# Logoi.net
KiCad netlist of a schematic drawn in EAGLE
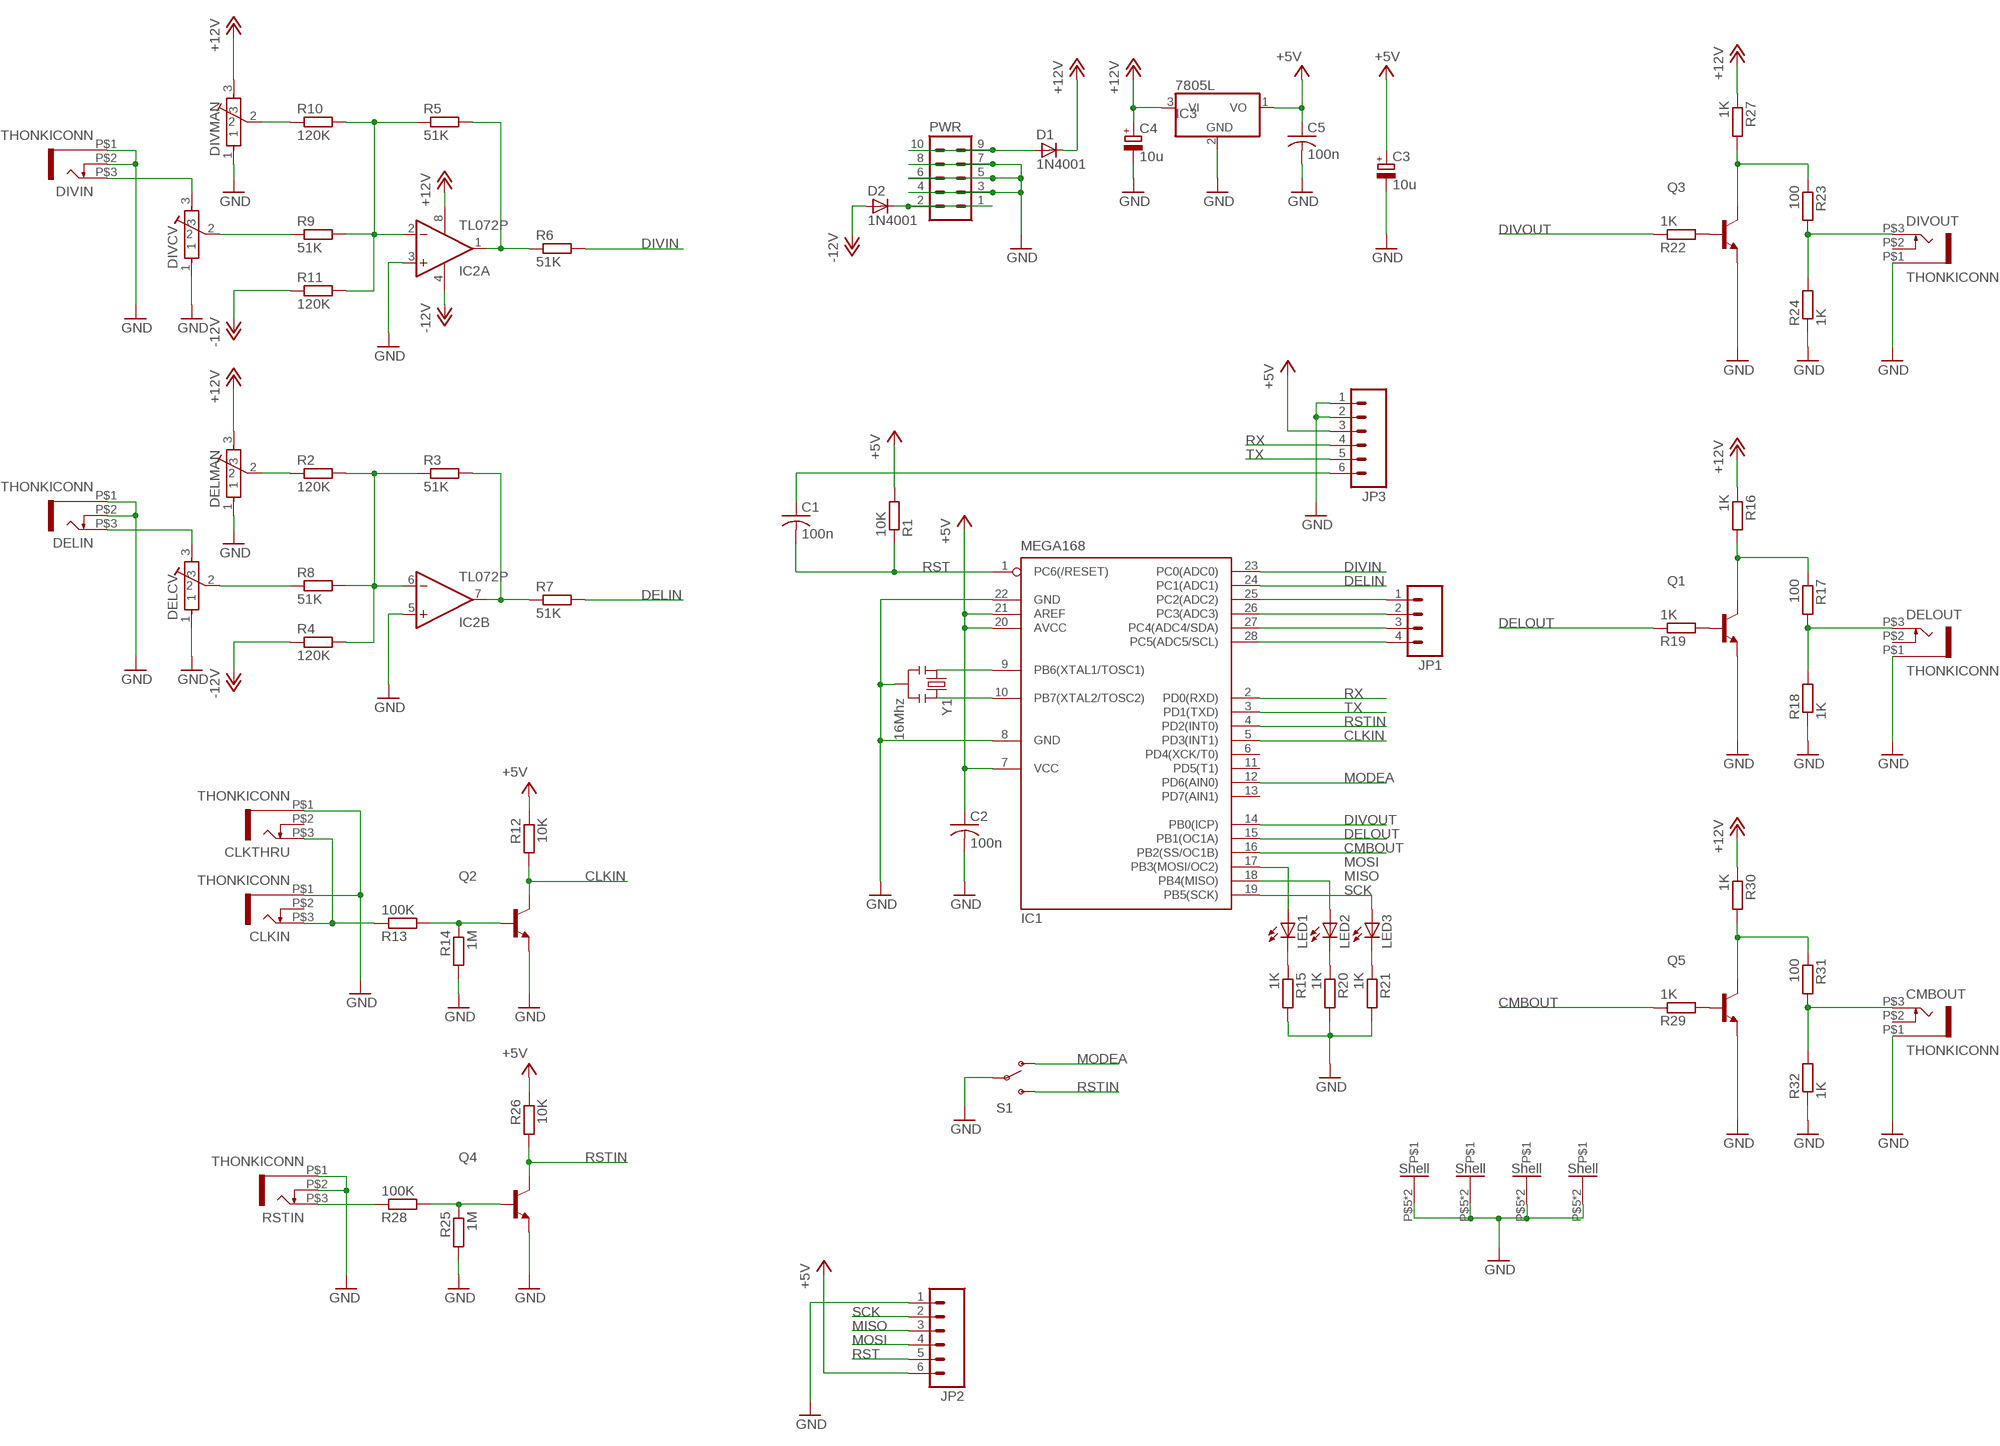
[diagram p0: schematic, sheet 1]

(export (version "E")
  (design (tool "Eeschema 10.0.6"))
  (components
    (comp (ref "C1")
      (value "100n")
      (footprint "eagle-import:C050-024X044")
      (libsource (lib "eagle-import") (part "C-US050-024X044"))
    )
    (comp (ref "C2")
      (value "100n")
      (footprint "eagle-import:C050-024X044")
      (libsource (lib "eagle-import") (part "C-US050-024X044"))
    )
    (comp (ref "C3")
      (value "10u")
      (footprint "eagle-import:E5-6")
      (libsource (lib "eagle-import") (part "CPOL-EUE5-6"))
    )
    (comp (ref "C4")
      (value "10u")
      (footprint "eagle-import:E5-6")
      (libsource (lib "eagle-import") (part "CPOL-EUE5-6"))
    )
    (comp (ref "C5")
      (value "100n")
      (footprint "eagle-import:C050-024X044")
      (libsource (lib "eagle-import") (part "C-US050-024X044"))
    )
    (comp (ref "CLKIN")
      (value "THONKICONN")
      (footprint "eagle-import:THONKICONN")
      (libsource (lib "eagle-import") (part "THONKICONN"))
    )
    (comp (ref "CLKTHRU")
      (value "THONKICONN")
      (footprint "eagle-import:THONKICONN")
      (libsource (lib "eagle-import") (part "THONKICONN"))
    )
    (comp (ref "CMBOUT")
      (value "THONKICONN")
      (footprint "eagle-import:THONKICONN")
      (libsource (lib "eagle-import") (part "THONKICONN"))
    )
    (comp (ref "D1")
      (value "1N4001")
      (footprint "eagle-import:DIODE-1N4001")
      (libsource (lib "eagle-import") (part "DIODE1N4001"))
    )
    (comp (ref "D2")
      (value "1N4001")
      (footprint "eagle-import:DIODE-1N4001")
      (libsource (lib "eagle-import") (part "DIODE1N4001"))
    )
    (comp (ref "DELCV")
      (value "POT-ALPS-RK09L1140")
      (footprint "eagle-import:POT-ALPS-RK09L1140")
      (libsource (lib "eagle-import") (part "POT-ALPS-RK09L1140"))
    )
    (comp (ref "DELIN")
      (value "THONKICONN")
      (footprint "eagle-import:THONKICONN")
      (libsource (lib "eagle-import") (part "THONKICONN"))
    )
    (comp (ref "DELMAN")
      (value "POT-ALPS-RK09L1140")
      (footprint "eagle-import:POT-ALPS-RK09L1140")
      (libsource (lib "eagle-import") (part "POT-ALPS-RK09L1140"))
    )
    (comp (ref "DELOUT")
      (value "THONKICONN")
      (footprint "eagle-import:THONKICONN")
      (libsource (lib "eagle-import") (part "THONKICONN"))
    )
    (comp (ref "DIVCV")
      (value "POT-ALPS-RK09L1140")
      (footprint "eagle-import:POT-ALPS-RK09L1140")
      (libsource (lib "eagle-import") (part "POT-ALPS-RK09L1140"))
    )
    (comp (ref "DIVIN")
      (value "THONKICONN")
      (footprint "eagle-import:THONKICONN")
      (libsource (lib "eagle-import") (part "THONKICONN"))
    )
    (comp (ref "DIVMAN")
      (value "POT-ALPS-RK09L1140")
      (footprint "eagle-import:POT-ALPS-RK09L1140")
      (libsource (lib "eagle-import") (part "POT-ALPS-RK09L1140"))
    )
    (comp (ref "DIVOUT")
      (value "THONKICONN")
      (footprint "eagle-import:THONKICONN")
      (libsource (lib "eagle-import") (part "THONKICONN"))
    )
    (comp (ref "IC1")
      (value "MEGA168")
      (footprint "eagle-import:DIL28-3")
      (libsource (lib "eagle-import") (part "MEGA8-P"))
    )
    (comp (ref "IC2")
      (value "TL072P")
      (footprint "eagle-import:DIL08")
      (libsource (lib "eagle-import") (part "TL072P"))
    )
    (comp (ref "IC3")
      (value "7805L")
      (footprint "eagle-import:TO92")
      (libsource (lib "eagle-import") (part "78L05"))
    )
    (comp (ref "JP1")
      (value "M04PTH")
      (footprint "eagle-import:1X04")
      (libsource (lib "eagle-import") (part "M04PTH"))
    )
    (comp (ref "JP2")
      (value "M06SIP")
      (footprint "eagle-import:1X06")
      (libsource (lib "eagle-import") (part "M06SIP"))
    )
    (comp (ref "JP3")
      (value "M06SIP")
      (footprint "eagle-import:1X06")
      (libsource (lib "eagle-import") (part "M06SIP"))
    )
    (comp (ref "LED1")
      (value "LED3MM")
      (footprint "eagle-import:LED3MM")
      (libsource (lib "eagle-import") (part "LED3MM"))
    )
    (comp (ref "LED2")
      (value "LED3MM")
      (footprint "eagle-import:LED3MM")
      (libsource (lib "eagle-import") (part "LED3MM"))
    )
    (comp (ref "LED3")
      (value "LED3MM")
      (footprint "eagle-import:LED3MM")
      (libsource (lib "eagle-import") (part "LED3MM"))
    )
    (comp (ref "PWR")
      (value "MA05-2")
      (footprint "eagle-import:MA05-2")
      (libsource (lib "eagle-import") (part "MA05-2"))
    )
    (comp (ref "Q1")
      (value "2N3904-NPN-TO92-EBC")
      (footprint "eagle-import:TO92-EBC")
      (libsource (lib "eagle-import") (part "-NPN-TO92-EBC2N3904"))
    )
    (comp (ref "Q2")
      (value "2N3904-NPN-TO92-EBC")
      (footprint "eagle-import:TO92-EBC")
      (libsource (lib "eagle-import") (part "-NPN-TO92-EBC2N3904"))
    )
    (comp (ref "Q3")
      (value "2N3904-NPN-TO92-EBC")
      (footprint "eagle-import:TO92-EBC")
      (libsource (lib "eagle-import") (part "-NPN-TO92-EBC2N3904"))
    )
    (comp (ref "Q4")
      (value "2N3904-NPN-TO92-EBC")
      (footprint "eagle-import:TO92-EBC")
      (libsource (lib "eagle-import") (part "-NPN-TO92-EBC2N3904"))
    )
    (comp (ref "Q5")
      (value "2N3904-NPN-TO92-EBC")
      (footprint "eagle-import:TO92-EBC")
      (libsource (lib "eagle-import") (part "-NPN-TO92-EBC2N3904"))
    )
    (comp (ref "R1")
      (value "10K")
      (footprint "eagle-import:0204_7")
      (libsource (lib "eagle-import") (part "R-EU_0204/7"))
    )
    (comp (ref "R2")
      (value "120K")
      (footprint "eagle-import:0204_7")
      (libsource (lib "eagle-import") (part "R-EU_0204/7"))
    )
    (comp (ref "R3")
      (value "51K")
      (footprint "eagle-import:0204_7")
      (libsource (lib "eagle-import") (part "R-EU_0204/7"))
    )
    (comp (ref "R4")
      (value "120K")
      (footprint "eagle-import:0204_7")
      (libsource (lib "eagle-import") (part "R-EU_0204/7"))
    )
    (comp (ref "R5")
      (value "51K")
      (footprint "eagle-import:0204_7")
      (libsource (lib "eagle-import") (part "R-EU_0204/7"))
    )
    (comp (ref "R6")
      (value "51K")
      (footprint "eagle-import:0204_7")
      (libsource (lib "eagle-import") (part "R-EU_0204/7"))
    )
    (comp (ref "R7")
      (value "51K")
      (footprint "eagle-import:0204_7")
      (libsource (lib "eagle-import") (part "R-EU_0204/7"))
    )
    (comp (ref "R8")
      (value "51K")
      (footprint "eagle-import:0204_7")
      (libsource (lib "eagle-import") (part "R-EU_0204/7"))
    )
    (comp (ref "R9")
      (value "51K")
      (footprint "eagle-import:0204_7")
      (libsource (lib "eagle-import") (part "R-EU_0204/7"))
    )
    (comp (ref "R10")
      (value "120K")
      (footprint "eagle-import:0204_7")
      (libsource (lib "eagle-import") (part "R-EU_0204/7"))
    )
    (comp (ref "R11")
      (value "120K")
      (footprint "eagle-import:0204_7")
      (libsource (lib "eagle-import") (part "R-EU_0204/7"))
    )
    (comp (ref "R12")
      (value "10K")
      (footprint "eagle-import:0204_7")
      (libsource (lib "eagle-import") (part "R-EU_0204/7"))
    )
    (comp (ref "R13")
      (value "100K")
      (footprint "eagle-import:0204_7")
      (libsource (lib "eagle-import") (part "R-EU_0204/7"))
    )
    (comp (ref "R14")
      (value "1M")
      (footprint "eagle-import:0204_7")
      (libsource (lib "eagle-import") (part "R-EU_0204/7"))
    )
    (comp (ref "R15")
      (value "1K")
      (footprint "eagle-import:0204_7")
      (libsource (lib "eagle-import") (part "R-EU_0204/7"))
    )
    (comp (ref "R16")
      (value "1K")
      (footprint "eagle-import:0204_7")
      (libsource (lib "eagle-import") (part "R-EU_0204/7"))
    )
    (comp (ref "R17")
      (value "100")
      (footprint "eagle-import:0204_7")
      (libsource (lib "eagle-import") (part "R-EU_0204/7"))
    )
    (comp (ref "R18")
      (value "1K")
      (footprint "eagle-import:0204_7")
      (libsource (lib "eagle-import") (part "R-EU_0204/7"))
    )
    (comp (ref "R19")
      (value "1K")
      (footprint "eagle-import:0204_7")
      (libsource (lib "eagle-import") (part "R-EU_0204/7"))
    )
    (comp (ref "R20")
      (value "1K")
      (footprint "eagle-import:0204_7")
      (libsource (lib "eagle-import") (part "R-EU_0204/7"))
    )
    (comp (ref "R21")
      (value "1K")
      (footprint "eagle-import:0204_7")
      (libsource (lib "eagle-import") (part "R-EU_0204/7"))
    )
    (comp (ref "R22")
      (value "1K")
      (footprint "eagle-import:0204_7")
      (libsource (lib "eagle-import") (part "R-EU_0204/7"))
    )
    (comp (ref "R23")
      (value "100")
      (footprint "eagle-import:0204_7")
      (libsource (lib "eagle-import") (part "R-EU_0204/7"))
    )
    (comp (ref "R24")
      (value "1K")
      (footprint "eagle-import:0204_7")
      (libsource (lib "eagle-import") (part "R-EU_0204/7"))
    )
    (comp (ref "R25")
      (value "1M")
      (footprint "eagle-import:0204_7")
      (libsource (lib "eagle-import") (part "R-EU_0204/7"))
    )
    (comp (ref "R26")
      (value "10K")
      (footprint "eagle-import:0204_7")
      (libsource (lib "eagle-import") (part "R-EU_0204/7"))
    )
    (comp (ref "R27")
      (value "1K")
      (footprint "eagle-import:0204_7")
      (libsource (lib "eagle-import") (part "R-EU_0204/7"))
    )
    (comp (ref "R28")
      (value "100K")
      (footprint "eagle-import:0204_7")
      (libsource (lib "eagle-import") (part "R-EU_0204/7"))
    )
    (comp (ref "R29")
      (value "1K")
      (footprint "eagle-import:0204_7")
      (libsource (lib "eagle-import") (part "R-EU_0204/7"))
    )
    (comp (ref "R30")
      (value "1K")
      (footprint "eagle-import:0204_7")
      (libsource (lib "eagle-import") (part "R-EU_0204/7"))
    )
    (comp (ref "R31")
      (value "100")
      (footprint "eagle-import:0204_7")
      (libsource (lib "eagle-import") (part "R-EU_0204/7"))
    )
    (comp (ref "R32")
      (value "1K")
      (footprint "eagle-import:0204_7")
      (libsource (lib "eagle-import") (part "R-EU_0204/7"))
    )
    (comp (ref "RSTIN")
      (value "THONKICONN")
      (footprint "eagle-import:THONKICONN")
      (libsource (lib "eagle-import") (part "THONKICONN"))
    )
    (comp (ref "S1")
      (value "SWITCH-SPST")
      (footprint "eagle-import:SWITCH-SPDT-SALECOM-T8014")
      (libsource (lib "eagle-import") (part "SWITCH-SPST"))
    )
    (comp (ref "Y1")
      (value "16Mhz")
      (footprint "eagle-import:RESONATOR-PTH")
      (libsource (lib "eagle-import") (part "RESONATORPTH"))
    )
  )
  (nets
    (net (code "1") (name "+5V") (class "Default")
      (node (ref "C2") (pin "1") (pinfunction "1_1") (pintype "passive"))
      (node (ref "C3") (pin "+") (pinfunction "+_+") (pintype "passive"))
      (node (ref "C5") (pin "1") (pinfunction "1_1") (pintype "passive"))
      (node (ref "IC1") (pin "20") (pinfunction "AVCC_20") (pintype "power_in"))
      (node (ref "IC1") (pin "21") (pinfunction "AREF_21") (pintype "passive"))
      (node (ref "IC1") (pin "7") (pinfunction "VCC_7") (pintype "power_in"))
      (node (ref "IC3") (pin "1") (pinfunction "VO_1") (pintype "passive"))
      (node (ref "JP2") (pin "6") (pinfunction "6_6") (pintype "passive"))
      (node (ref "JP3") (pin "3") (pinfunction "3_3") (pintype "passive"))
      (node (ref "R1") (pin "2") (pinfunction "2_2") (pintype "passive"))
      (node (ref "R12") (pin "1") (pinfunction "1_1") (pintype "passive"))
      (node (ref "R26") (pin "1") (pinfunction "1_1") (pintype "passive"))
    )
    (net (code "2") (name "+12V") (class "Default")
      (node (ref "C4") (pin "+") (pinfunction "+_+") (pintype "passive"))
      (node (ref "D1") (pin "C") (pinfunction "C_C") (pintype "passive"))
      (node (ref "DELMAN") (pin "3") (pinfunction "3_3") (pintype "bidirectional"))
      (node (ref "DIVMAN") (pin "3") (pinfunction "3_3") (pintype "bidirectional"))
      (node (ref "IC2") (pin "8") (pinfunction "V+_8") (pintype "power_in"))
      (node (ref "IC3") (pin "3") (pinfunction "VI_3") (pintype "input"))
      (node (ref "R16") (pin "1") (pinfunction "1_1") (pintype "passive"))
      (node (ref "R27") (pin "1") (pinfunction "1_1") (pintype "passive"))
      (node (ref "R30") (pin "1") (pinfunction "1_1") (pintype "passive"))
    )
    (net (code "3") (name "-12V") (class "Default")
      (node (ref "D2") (pin "A") (pinfunction "A_A") (pintype "passive"))
      (node (ref "IC2") (pin "4") (pinfunction "V-_4") (pintype "power_in"))
      (node (ref "R11") (pin "1") (pinfunction "1_1") (pintype "passive"))
      (node (ref "R4") (pin "1") (pinfunction "1_1") (pintype "passive"))
    )
    (net (code "4") (name "/CLKIN") (class "Default")
      (node (ref "IC1") (pin "5") (pinfunction "PD3(INT1)_5") (pintype "bidirectional"))
      (node (ref "Q2") (pin "C") (pinfunction "C_C") (pintype "passive"))
      (node (ref "R12") (pin "2") (pinfunction "2_2") (pintype "passive"))
    )
    (net (code "5") (name "/CMBOUT") (class "Default")
      (node (ref "IC1") (pin "16") (pinfunction "PB2(SS/OC1B)_16") (pintype "bidirectional"))
      (node (ref "R29") (pin "1") (pinfunction "1_1") (pintype "passive"))
    )
    (net (code "6") (name "/DELIN") (class "Default")
      (node (ref "IC1") (pin "24") (pinfunction "PC1(ADC1)_24") (pintype "bidirectional"))
      (node (ref "R7") (pin "2") (pinfunction "2_2") (pintype "passive"))
    )
    (net (code "7") (name "/DELOUT") (class "Default")
      (node (ref "IC1") (pin "15") (pinfunction "PB1(OC1A)_15") (pintype "bidirectional"))
      (node (ref "R19") (pin "1") (pinfunction "1_1") (pintype "passive"))
    )
    (net (code "8") (name "/DIVIN") (class "Default")
      (node (ref "IC1") (pin "23") (pinfunction "PC0(ADC0)_23") (pintype "bidirectional"))
      (node (ref "R6") (pin "2") (pinfunction "2_2") (pintype "passive"))
    )
    (net (code "9") (name "/DIVOUT") (class "Default")
      (node (ref "IC1") (pin "14") (pinfunction "PB0(ICP)_14") (pintype "bidirectional"))
      (node (ref "R22") (pin "1") (pinfunction "1_1") (pintype "passive"))
    )
    (net (code "10") (name "/MISO") (class "Default")
      (node (ref "IC1") (pin "18") (pinfunction "PB4(MISO)_18") (pintype "bidirectional"))
      (node (ref "JP2") (pin "3") (pinfunction "3_3") (pintype "passive"))
      (node (ref "LED2") (pin "A") (pinfunction "A_A") (pintype "passive"))
    )
    (net (code "11") (name "/MODEA") (class "Default")
      (node (ref "IC1") (pin "12") (pinfunction "PD6(AIN0)_12") (pintype "bidirectional"))
      (node (ref "S1") (pin "1") (pinfunction "O_1") (pintype "passive"))
    )
    (net (code "12") (name "/MOSI") (class "Default")
      (node (ref "IC1") (pin "17") (pinfunction "PB3(MOSI/OC2)_17") (pintype "bidirectional"))
      (node (ref "JP2") (pin "4") (pinfunction "4_4") (pintype "passive"))
      (node (ref "LED1") (pin "A") (pinfunction "A_A") (pintype "passive"))
    )
    (net (code "13") (name "/RST") (class "Default")
      (node (ref "C1") (pin "2") (pinfunction "2_2") (pintype "passive"))
      (node (ref "IC1") (pin "1") (pinfunction "PC6(/RESET)_1") (pintype "bidirectional"))
      (node (ref "JP2") (pin "5") (pinfunction "5_5") (pintype "passive"))
      (node (ref "R1") (pin "1") (pinfunction "1_1") (pintype "passive"))
    )
    (net (code "14") (name "/RSTIN") (class "Default")
      (node (ref "IC1") (pin "4") (pinfunction "PD2(INT0)_4") (pintype "bidirectional"))
      (node (ref "Q4") (pin "C") (pinfunction "C_C") (pintype "passive"))
      (node (ref "R26") (pin "2") (pinfunction "2_2") (pintype "passive"))
      (node (ref "S1") (pin "3") (pinfunction "S_3") (pintype "passive"))
    )
    (net (code "15") (name "/RX") (class "Default")
      (node (ref "IC1") (pin "2") (pinfunction "PD0(RXD)_2") (pintype "bidirectional"))
      (node (ref "JP3") (pin "4") (pinfunction "4_4") (pintype "passive"))
    )
    (net (code "16") (name "/SCK") (class "Default")
      (node (ref "IC1") (pin "19") (pinfunction "PB5(SCK)_19") (pintype "bidirectional"))
      (node (ref "JP2") (pin "2") (pinfunction "2_2") (pintype "passive"))
      (node (ref "LED3") (pin "A") (pinfunction "A_A") (pintype "passive"))
    )
    (net (code "17") (name "/TX") (class "Default")
      (node (ref "IC1") (pin "3") (pinfunction "PD1(TXD)_3") (pintype "bidirectional"))
      (node (ref "JP3") (pin "5") (pinfunction "5_5") (pintype "passive"))
    )
    (net (code "18") (name "GND") (class "Default")
      (node (ref "C2") (pin "2") (pinfunction "2_2") (pintype "passive"))
      (node (ref "C3") (pin "-") (pinfunction "-_-") (pintype "passive"))
      (node (ref "C4") (pin "-") (pinfunction "-_-") (pintype "passive"))
      (node (ref "C5") (pin "2") (pinfunction "2_2") (pintype "passive"))
      (node (ref "CLKIN") (pin "P$1") (pinfunction "5_P$1") (pintype "passive"))
      (node (ref "CLKTHRU") (pin "P$1") (pinfunction "5_P$1") (pintype "passive"))
      (node (ref "CMBOUT") (pin "P$1") (pinfunction "5_P$1") (pintype "passive"))
      (node (ref "DELCV") (pin "1") (pinfunction "1_1") (pintype "bidirectional"))
      (node (ref "DELCV") (pin "P$5") (pinfunction "P$1_P$5") (pintype "bidirectional"))
      (node (ref "DELCV") (pin "P$6") (pinfunction "P$1_P$6") (pintype "bidirectional"))
      (node (ref "DELIN") (pin "P$1") (pinfunction "5_P$1") (pintype "passive"))
      (node (ref "DELIN") (pin "P$2") (pinfunction "4_P$2") (pintype "passive"))
      (node (ref "DELMAN") (pin "1") (pinfunction "1_1") (pintype "bidirectional"))
      (node (ref "DELMAN") (pin "P$5") (pinfunction "P$1_P$5") (pintype "bidirectional"))
      (node (ref "DELMAN") (pin "P$6") (pinfunction "P$1_P$6") (pintype "bidirectional"))
      (node (ref "DELOUT") (pin "P$1") (pinfunction "5_P$1") (pintype "passive"))
      (node (ref "DIVCV") (pin "1") (pinfunction "1_1") (pintype "bidirectional"))
      (node (ref "DIVCV") (pin "P$5") (pinfunction "P$1_P$5") (pintype "bidirectional"))
      (node (ref "DIVCV") (pin "P$6") (pinfunction "P$1_P$6") (pintype "bidirectional"))
      (node (ref "DIVIN") (pin "P$1") (pinfunction "5_P$1") (pintype "passive"))
      (node (ref "DIVIN") (pin "P$2") (pinfunction "4_P$2") (pintype "passive"))
      (node (ref "DIVMAN") (pin "1") (pinfunction "1_1") (pintype "bidirectional"))
      (node (ref "DIVMAN") (pin "P$5") (pinfunction "P$1_P$5") (pintype "bidirectional"))
      (node (ref "DIVMAN") (pin "P$6") (pinfunction "P$1_P$6") (pintype "bidirectional"))
      (node (ref "DIVOUT") (pin "P$1") (pinfunction "5_P$1") (pintype "passive"))
      (node (ref "IC1") (pin "22") (pinfunction "GND_22") (pintype "power_in"))
      (node (ref "IC1") (pin "8") (pinfunction "GND_8") (pintype "power_in"))
      (node (ref "IC2") (pin "3") (pinfunction "+IN_3") (pintype "input"))
      (node (ref "IC2") (pin "5") (pinfunction "+IN_5") (pintype "input"))
      (node (ref "IC3") (pin "2") (pinfunction "GND_2") (pintype "passive"))
      (node (ref "JP2") (pin "1") (pinfunction "1_1") (pintype "passive"))
      (node (ref "JP3") (pin "1") (pinfunction "1_1") (pintype "passive"))
      (node (ref "JP3") (pin "2") (pinfunction "2_2") (pintype "passive"))
      (node (ref "PWR") (pin "3") (pinfunction "3_3") (pintype "passive"))
      (node (ref "PWR") (pin "4") (pinfunction "4_4") (pintype "passive"))
      (node (ref "PWR") (pin "5") (pinfunction "5_5") (pintype "passive"))
      (node (ref "PWR") (pin "6") (pinfunction "6_6") (pintype "passive"))
      (node (ref "PWR") (pin "7") (pinfunction "7_7") (pintype "passive"))
      (node (ref "PWR") (pin "8") (pinfunction "8_8") (pintype "passive"))
      (node (ref "Q1") (pin "E") (pinfunction "E_E") (pintype "passive"))
      (node (ref "Q2") (pin "E") (pinfunction "E_E") (pintype "passive"))
      (node (ref "Q3") (pin "E") (pinfunction "E_E") (pintype "passive"))
      (node (ref "Q4") (pin "E") (pinfunction "E_E") (pintype "passive"))
      (node (ref "Q5") (pin "E") (pinfunction "E_E") (pintype "passive"))
      (node (ref "R14") (pin "2") (pinfunction "2_2") (pintype "passive"))
      (node (ref "R15") (pin "2") (pinfunction "2_2") (pintype "passive"))
      (node (ref "R18") (pin "1") (pinfunction "1_1") (pintype "passive"))
      (node (ref "R20") (pin "2") (pinfunction "2_2") (pintype "passive"))
      (node (ref "R21") (pin "2") (pinfunction "2_2") (pintype "passive"))
      (node (ref "R24") (pin "1") (pinfunction "1_1") (pintype "passive"))
      (node (ref "R25") (pin "2") (pinfunction "2_2") (pintype "passive"))
      (node (ref "R32") (pin "1") (pinfunction "1_1") (pintype "passive"))
      (node (ref "RSTIN") (pin "P$1") (pinfunction "5_P$1") (pintype "passive"))
      (node (ref "RSTIN") (pin "P$2") (pinfunction "4_P$2") (pintype "passive"))
      (node (ref "S1") (pin "2") (pinfunction "P_2") (pintype "passive"))
      (node (ref "Y1") (pin "2") (pinfunction "2_2") (pintype "passive"))
    )
    (net (code "19") (name "Net-(C1-Pad1)") (class "Default")
      (node (ref "C1") (pin "1") (pinfunction "1_1") (pintype "passive"))
      (node (ref "JP3") (pin "6") (pinfunction "6_6") (pintype "passive"))
    )
    (net (code "20") (name "Net-(CLKIN-3)") (class "Default")
      (node (ref "CLKIN") (pin "P$3") (pinfunction "3_P$3") (pintype "passive"))
      (node (ref "CLKTHRU") (pin "P$3") (pinfunction "3_P$3") (pintype "passive"))
      (node (ref "R13") (pin "1") (pinfunction "1_1") (pintype "passive"))
    )
    (net (code "21") (name "Net-(CMBOUT-3)") (class "Default")
      (node (ref "CMBOUT") (pin "P$3") (pinfunction "3_P$3") (pintype "passive"))
      (node (ref "R31") (pin "2") (pinfunction "2_2") (pintype "passive"))
      (node (ref "R32") (pin "2") (pinfunction "2_2") (pintype "passive"))
    )
    (net (code "22") (name "Net-(D1-PadA)") (class "Default")
      (node (ref "D1") (pin "A") (pinfunction "A_A") (pintype "passive"))
      (node (ref "PWR") (pin "10") (pinfunction "10_10") (pintype "passive"))
      (node (ref "PWR") (pin "9") (pinfunction "9_9") (pintype "passive"))
    )
    (net (code "23") (name "Net-(D2-PadC)") (class "Default")
      (node (ref "D2") (pin "C") (pinfunction "C_C") (pintype "passive"))
      (node (ref "PWR") (pin "1") (pinfunction "1_1") (pintype "passive"))
      (node (ref "PWR") (pin "2") (pinfunction "2_2") (pintype "passive"))
    )
    (net (code "24") (name "Net-(DELCV-Pad2)") (class "Default")
      (node (ref "DELCV") (pin "2") (pinfunction "2_2") (pintype "bidirectional"))
      (node (ref "R8") (pin "1") (pinfunction "1_1") (pintype "passive"))
    )
    (net (code "25") (name "Net-(DELIN-3)") (class "Default")
      (node (ref "DELCV") (pin "3") (pinfunction "3_3") (pintype "bidirectional"))
      (node (ref "DELIN") (pin "P$3") (pinfunction "3_P$3") (pintype "passive"))
    )
    (net (code "26") (name "Net-(DELMAN-Pad2)") (class "Default")
      (node (ref "DELMAN") (pin "2") (pinfunction "2_2") (pintype "bidirectional"))
      (node (ref "R2") (pin "1") (pinfunction "1_1") (pintype "passive"))
    )
    (net (code "27") (name "Net-(DELOUT-3)") (class "Default")
      (node (ref "DELOUT") (pin "P$3") (pinfunction "3_P$3") (pintype "passive"))
      (node (ref "R17") (pin "2") (pinfunction "2_2") (pintype "passive"))
      (node (ref "R18") (pin "2") (pinfunction "2_2") (pintype "passive"))
    )
    (net (code "28") (name "Net-(DIVCV-Pad2)") (class "Default")
      (node (ref "DIVCV") (pin "2") (pinfunction "2_2") (pintype "bidirectional"))
      (node (ref "R9") (pin "1") (pinfunction "1_1") (pintype "passive"))
    )
    (net (code "29") (name "Net-(DIVIN-3)") (class "Default")
      (node (ref "DIVCV") (pin "3") (pinfunction "3_3") (pintype "bidirectional"))
      (node (ref "DIVIN") (pin "P$3") (pinfunction "3_P$3") (pintype "passive"))
    )
    (net (code "30") (name "Net-(DIVMAN-Pad2)") (class "Default")
      (node (ref "DIVMAN") (pin "2") (pinfunction "2_2") (pintype "bidirectional"))
      (node (ref "R10") (pin "1") (pinfunction "1_1") (pintype "passive"))
    )
    (net (code "31") (name "Net-(DIVOUT-3)") (class "Default")
      (node (ref "DIVOUT") (pin "P$3") (pinfunction "3_P$3") (pintype "passive"))
      (node (ref "R23") (pin "2") (pinfunction "2_2") (pintype "passive"))
      (node (ref "R24") (pin "2") (pinfunction "2_2") (pintype "passive"))
    )
    (net (code "32") (name "Net-(IC1-PB6(XTAL1{slash}TOSC1))") (class "Default")
      (node (ref "IC1") (pin "9") (pinfunction "PB6(XTAL1/TOSC1)_9") (pintype "bidirectional"))
      (node (ref "Y1") (pin "1") (pinfunction "1_1") (pintype "passive"))
    )
    (net (code "33") (name "Net-(IC1-PB7(XTAL2{slash}TOSC2))") (class "Default")
      (node (ref "IC1") (pin "10") (pinfunction "PB7(XTAL2/TOSC2)_10") (pintype "bidirectional"))
      (node (ref "Y1") (pin "3") (pinfunction "3_3") (pintype "passive"))
    )
    (net (code "34") (name "Net-(IC1-PC2(ADC2))") (class "Default")
      (node (ref "IC1") (pin "25") (pinfunction "PC2(ADC2)_25") (pintype "bidirectional"))
      (node (ref "JP1") (pin "1") (pinfunction "1_1") (pintype "passive"))
    )
    (net (code "35") (name "Net-(IC1-PC3(ADC3))") (class "Default")
      (node (ref "IC1") (pin "26") (pinfunction "PC3(ADC3)_26") (pintype "bidirectional"))
      (node (ref "JP1") (pin "2") (pinfunction "2_2") (pintype "passive"))
    )
    (net (code "36") (name "Net-(IC1-PC4(ADC4{slash}SDA))") (class "Default")
      (node (ref "IC1") (pin "27") (pinfunction "PC4(ADC4/SDA)_27") (pintype "bidirectional"))
      (node (ref "JP1") (pin "3") (pinfunction "3_3") (pintype "passive"))
    )
    (net (code "37") (name "Net-(IC1-PC5(ADC5{slash}SCL))") (class "Default")
      (node (ref "IC1") (pin "28") (pinfunction "PC5(ADC5/SCL)_28") (pintype "bidirectional"))
      (node (ref "JP1") (pin "4") (pinfunction "4_4") (pintype "passive"))
    )
    (net (code "38") (name "Net-(IC2A--IN)") (class "Default")
      (node (ref "IC2") (pin "2") (pinfunction "-IN_2") (pintype "input"))
      (node (ref "R10") (pin "2") (pinfunction "2_2") (pintype "passive"))
      (node (ref "R11") (pin "2") (pinfunction "2_2") (pintype "passive"))
      (node (ref "R5") (pin "1") (pinfunction "1_1") (pintype "passive"))
      (node (ref "R9") (pin "2") (pinfunction "2_2") (pintype "passive"))
    )
    (net (code "39") (name "Net-(IC2A-OUT)") (class "Default")
      (node (ref "IC2") (pin "1") (pinfunction "OUT_1") (pintype "output"))
      (node (ref "R5") (pin "2") (pinfunction "2_2") (pintype "passive"))
      (node (ref "R6") (pin "1") (pinfunction "1_1") (pintype "passive"))
    )
    (net (code "40") (name "Net-(IC2B--IN)") (class "Default")
      (node (ref "IC2") (pin "6") (pinfunction "-IN_6") (pintype "input"))
      (node (ref "R2") (pin "2") (pinfunction "2_2") (pintype "passive"))
      (node (ref "R3") (pin "1") (pinfunction "1_1") (pintype "passive"))
      (node (ref "R4") (pin "2") (pinfunction "2_2") (pintype "passive"))
      (node (ref "R8") (pin "2") (pinfunction "2_2") (pintype "passive"))
    )
    (net (code "41") (name "Net-(IC2B-OUT)") (class "Default")
      (node (ref "IC2") (pin "7") (pinfunction "OUT_7") (pintype "output"))
      (node (ref "R3") (pin "2") (pinfunction "2_2") (pintype "passive"))
      (node (ref "R7") (pin "1") (pinfunction "1_1") (pintype "passive"))
    )
    (net (code "42") (name "Net-(LED1-C)") (class "Default")
      (node (ref "LED1") (pin "K") (pinfunction "C_K") (pintype "passive"))
      (node (ref "R15") (pin "1") (pinfunction "1_1") (pintype "passive"))
    )
    (net (code "43") (name "Net-(LED2-C)") (class "Default")
      (node (ref "LED2") (pin "K") (pinfunction "C_K") (pintype "passive"))
      (node (ref "R20") (pin "1") (pinfunction "1_1") (pintype "passive"))
    )
    (net (code "44") (name "Net-(LED3-C)") (class "Default")
      (node (ref "LED3") (pin "K") (pinfunction "C_K") (pintype "passive"))
      (node (ref "R21") (pin "1") (pinfunction "1_1") (pintype "passive"))
    )
    (net (code "45") (name "Net-(Q1-PadB)") (class "Default")
      (node (ref "Q1") (pin "B") (pinfunction "B_B") (pintype "passive"))
      (node (ref "R19") (pin "2") (pinfunction "2_2") (pintype "passive"))
    )
    (net (code "46") (name "Net-(Q1-PadC)") (class "Default")
      (node (ref "Q1") (pin "C") (pinfunction "C_C") (pintype "passive"))
      (node (ref "R16") (pin "2") (pinfunction "2_2") (pintype "passive"))
      (node (ref "R17") (pin "1") (pinfunction "1_1") (pintype "passive"))
    )
    (net (code "47") (name "Net-(Q2-PadB)") (class "Default")
      (node (ref "Q2") (pin "B") (pinfunction "B_B") (pintype "passive"))
      (node (ref "R13") (pin "2") (pinfunction "2_2") (pintype "passive"))
      (node (ref "R14") (pin "1") (pinfunction "1_1") (pintype "passive"))
    )
    (net (code "48") (name "Net-(Q3-PadB)") (class "Default")
      (node (ref "Q3") (pin "B") (pinfunction "B_B") (pintype "passive"))
      (node (ref "R22") (pin "2") (pinfunction "2_2") (pintype "passive"))
    )
    (net (code "49") (name "Net-(Q3-PadC)") (class "Default")
      (node (ref "Q3") (pin "C") (pinfunction "C_C") (pintype "passive"))
      (node (ref "R23") (pin "1") (pinfunction "1_1") (pintype "passive"))
      (node (ref "R27") (pin "2") (pinfunction "2_2") (pintype "passive"))
    )
    (net (code "50") (name "Net-(Q4-PadB)") (class "Default")
      (node (ref "Q4") (pin "B") (pinfunction "B_B") (pintype "passive"))
      (node (ref "R25") (pin "1") (pinfunction "1_1") (pintype "passive"))
      (node (ref "R28") (pin "2") (pinfunction "2_2") (pintype "passive"))
    )
    (net (code "51") (name "Net-(Q5-PadB)") (class "Default")
      (node (ref "Q5") (pin "B") (pinfunction "B_B") (pintype "passive"))
      (node (ref "R29") (pin "2") (pinfunction "2_2") (pintype "passive"))
    )
    (net (code "52") (name "Net-(Q5-PadC)") (class "Default")
      (node (ref "Q5") (pin "C") (pinfunction "C_C") (pintype "passive"))
      (node (ref "R30") (pin "2") (pinfunction "2_2") (pintype "passive"))
      (node (ref "R31") (pin "1") (pinfunction "1_1") (pintype "passive"))
    )
    (net (code "53") (name "Net-(RSTIN-3)") (class "Default")
      (node (ref "R28") (pin "1") (pinfunction "1_1") (pintype "passive"))
      (node (ref "RSTIN") (pin "P$3") (pinfunction "3_P$3") (pintype "passive"))
    )
    (net (code "54") (name "unconnected-(CLKIN-4-PadP$2)") (class "Default")
      (node (ref "CLKIN") (pin "P$2") (pinfunction "4_P$2") (pintype "passive"))
    )
    (net (code "55") (name "unconnected-(CLKTHRU-4-PadP$2)") (class "Default")
      (node (ref "CLKTHRU") (pin "P$2") (pinfunction "4_P$2") (pintype "passive"))
    )
    (net (code "56") (name "unconnected-(CMBOUT-4-PadP$2)") (class "Default")
      (node (ref "CMBOUT") (pin "P$2") (pinfunction "4_P$2") (pintype "passive"))
    )
    (net (code "57") (name "unconnected-(DELOUT-4-PadP$2)") (class "Default")
      (node (ref "DELOUT") (pin "P$2") (pinfunction "4_P$2") (pintype "passive"))
    )
    (net (code "58") (name "unconnected-(DIVOUT-4-PadP$2)") (class "Default")
      (node (ref "DIVOUT") (pin "P$2") (pinfunction "4_P$2") (pintype "passive"))
    )
    (net (code "59") (name "unconnected-(IC1-PD4(XCK{slash}T0)-Pad6)") (class "Default")
      (node (ref "IC1") (pin "6") (pinfunction "PD4(XCK/T0)_6") (pintype "bidirectional"))
    )
    (net (code "60") (name "unconnected-(IC1-PD5(T1)-Pad11)") (class "Default")
      (node (ref "IC1") (pin "11") (pinfunction "PD5(T1)_11") (pintype "bidirectional"))
    )
    (net (code "61") (name "unconnected-(IC1-PD7(AIN1)-Pad13)") (class "Default")
      (node (ref "IC1") (pin "13") (pinfunction "PD7(AIN1)_13") (pintype "bidirectional"))
    )
  )
)
